# power.net
KiCad netlist of a schematic drawn in Altium Designer
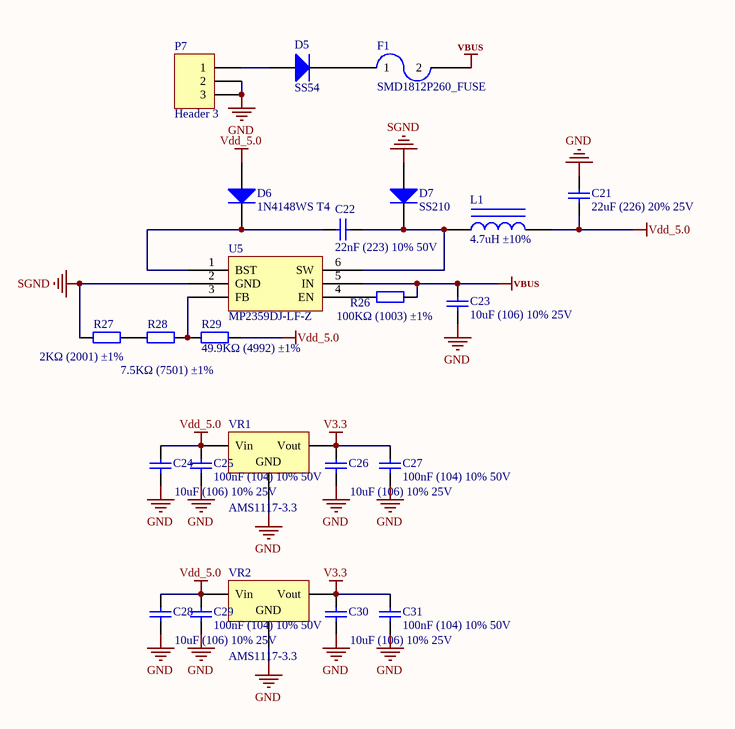
[diagram p0: power.SchDoc]

(export (version "E")
  (design (tool "Eeschema 10.0.6"))
  (components
    (comp (ref "C21")
      (value "22uF (226) 20% 25V")
      (footprint "0805_C")
      (description "贴片电容")
      (libsource (lib "Miscellaneous Devices LC") (part "0805 22uF (226) 20% 25V"))
    )
    (comp (ref "C22")
      (value "22nF (223) 10% 50V")
      (footprint "0603_C")
      (description "贴片电容")
      (libsource (lib "Miscellaneous Devices LC") (part "0603 22nF (223) 10% 50V"))
    )
    (comp (ref "C23")
      (value "10uF (106) 10% 25V")
      (footprint "0805_C")
      (description "贴片电容")
      (libsource (lib "Miscellaneous Devices LC") (part "0805 10uF (106) 10% 25V"))
    )
    (comp (ref "C24")
      (value "10uF (106) 10% 25V")
      (footprint "0805_C")
      (description "贴片电容")
      (libsource (lib "Miscellaneous Devices LC") (part "0805 10uF (106) 10% 25V"))
    )
    (comp (ref "C25")
      (value "100nF (104) 10% 50V")
      (footprint "0603_C")
      (description "贴片电容")
      (libsource (lib "Miscellaneous Devices LC") (part "0603 100nF (104) 10% 50V"))
    )
    (comp (ref "C26")
      (value "10uF (106) 10% 25V")
      (footprint "0805_C")
      (description "贴片电容")
      (libsource (lib "Miscellaneous Devices LC") (part "0805 10uF (106) 10% 25V"))
    )
    (comp (ref "C27")
      (value "100nF (104) 10% 50V")
      (footprint "0603_C")
      (description "贴片电容")
      (libsource (lib "Miscellaneous Devices LC") (part "0603 100nF (104) 10% 50V"))
    )
    (comp (ref "C28")
      (value "10uF (106) 10% 25V")
      (footprint "0805_C")
      (description "贴片电容")
      (libsource (lib "Miscellaneous Devices LC") (part "0805 10uF (106) 10% 25V"))
    )
    (comp (ref "C29")
      (value "100nF (104) 10% 50V")
      (footprint "0603_C")
      (description "贴片电容")
      (libsource (lib "Miscellaneous Devices LC") (part "0603 100nF (104) 10% 50V"))
    )
    (comp (ref "C30")
      (value "10uF (106) 10% 25V")
      (footprint "0805_C")
      (description "贴片电容")
      (libsource (lib "Miscellaneous Devices LC") (part "0805 10uF (106) 10% 25V"))
    )
    (comp (ref "C31")
      (value "100nF (104) 10% 50V")
      (footprint "0603_C")
      (description "贴片电容")
      (libsource (lib "Miscellaneous Devices LC") (part "0603 100nF (104) 10% 50V"))
    )
    (comp (ref "D5")
      (value "SS54")
      (footprint "SMA(DO-214AC)_S1")
      (description "二极管")
      (libsource (lib "Miscellaneous Devices LC") (part "SMA(DO-214AC) SS54"))
    )
    (comp (ref "D6")
      (value "1N4148WS T4")
      (footprint "SOD-323")
      (description "二极管")
      (libsource (lib "Miscellaneous Devices LC") (part "SOD-323 1N4148WS T4"))
    )
    (comp (ref "D7")
      (value "SS210")
      (footprint "SMA(DO-214AC)_S1")
      (description "二极管")
      (libsource (lib "Miscellaneous Devices LC") (part "SMA(DO-214AC) SS210"))
    )
    (comp (ref "F1")
      (value "SMD1812P260_FUSE")
      (footprint "SMD1812P260")
      (libsource (lib "mylib") (part "SMD1812P260_FUSE"))
    )
    (comp (ref "L1")
      (value "4.7uH ±10%")
      (footprint "L_4030")
      (description "贴片电感")
      (libsource (lib "Miscellaneous Devices LC") (part "0603 4.7uH 10%"))
    )
    (comp (ref "P7")
      (value "Header 3")
      (footprint "DC-005")
      (description "Header, 3-Pin")
      (fields (field (name "PUBLISHER") "Altium Limited"))
      (libsource (lib "Miscellaneous Connectors") (part "Header 3"))
    )
    (comp (ref "R26")
      (value "100KΩ (1003) ±1%")
      (footprint "0603_R")
      (description "贴片电阻")
      (libsource (lib "Miscellaneous Devices LC") (part "0603 100KΩ (1003) 1%"))
    )
    (comp (ref "R27")
      (value "2KΩ (2001) ±1%")
      (footprint "0603_R")
      (description "贴片电阻")
      (libsource (lib "Miscellaneous Devices LC") (part "0603 2KΩ (2001) 1%"))
    )
    (comp (ref "R28")
      (value "7.5KΩ (7501) ±1%")
      (footprint "0603_R")
      (description "贴片电阻")
      (libsource (lib "Miscellaneous Devices LC") (part "0603 7.5KΩ (7501) 1%"))
    )
    (comp (ref "R29")
      (value "49.9KΩ (4992) ±1%")
      (footprint "0603_R")
      (description "贴片电阻")
      (libsource (lib "Miscellaneous Devices LC") (part "0603 49.9KΩ (4992) 1%"))
    )
    (comp (ref "U5")
      (value "MP2359DJ-LF-Z")
      (footprint "SOT-23-6")
      (description "DC-DC芯片")
      (libsource (lib "Miscellaneous Devices LC") (part "MP2359DJ-LF-Z_[C14259]"))
    )
    (comp (ref "VR1")
      (value "AMS1117-3.3")
      (footprint "SOT-223")
      (description "低压差线性稳压(LDO)")
      (libsource (lib "Miscellaneous Devices LC") (part "SOT-223 AMS1117-3.3"))
    )
    (comp (ref "VR2")
      (value "AMS1117-3.3")
      (footprint "SOT-223")
      (description "低压差线性稳压(LDO)")
      (libsource (lib "Miscellaneous Devices LC") (part "SOT-223 AMS1117-3.3"))
    )
  )
  (nets
    (net (code "1") (name "GND") (class "Default")
      (node (ref "C21") (pin "2") (pinfunction "2_2") (pintype "passive"))
      (node (ref "C23") (pin "1") (pinfunction "1_1") (pintype "passive"))
      (node (ref "C24") (pin "1") (pinfunction "1_1") (pintype "passive"))
      (node (ref "C25") (pin "1") (pinfunction "1_1") (pintype "passive"))
      (node (ref "C26") (pin "1") (pinfunction "1_1") (pintype "passive"))
      (node (ref "C27") (pin "1") (pinfunction "1_1") (pintype "passive"))
      (node (ref "C28") (pin "1") (pinfunction "1_1") (pintype "passive"))
      (node (ref "C29") (pin "1") (pinfunction "1_1") (pintype "passive"))
      (node (ref "C30") (pin "1") (pinfunction "1_1") (pintype "passive"))
      (node (ref "C31") (pin "1") (pinfunction "1_1") (pintype "passive"))
      (node (ref "P7") (pin "2") (pinfunction "2_2") (pintype "passive"))
      (node (ref "P7") (pin "3") (pinfunction "3_3") (pintype "passive"))
      (node (ref "VR1") (pin "1") (pinfunction "GND_1") (pintype "passive"))
      (node (ref "VR2") (pin "1") (pinfunction "GND_1") (pintype "passive"))
    )
    (net (code "2") (name "Net-(D5-A)") (class "Default")
      (node (ref "D5") (pin "1") (pinfunction "A_1") (pintype "passive"))
      (node (ref "P7") (pin "1") (pinfunction "1_1") (pintype "passive"))
    )
    (net (code "3") (name "Net-(D5-K)") (class "Default")
      (node (ref "D5") (pin "2") (pinfunction "K_2") (pintype "passive"))
      (node (ref "F1") (pin "1") (pinfunction "1_1") (pintype "passive"))
    )
    (net (code "4") (name "Net-(D6-K)") (class "Default")
      (node (ref "C22") (pin "1") (pinfunction "1_1") (pintype "passive"))
      (node (ref "D6") (pin "2") (pinfunction "K_2") (pintype "passive"))
      (node (ref "U5") (pin "1") (pinfunction "BST_1") (pintype "passive"))
    )
    (net (code "5") (name "Net-(D7-K)") (class "Default")
      (node (ref "C22") (pin "2") (pinfunction "2_2") (pintype "passive"))
      (node (ref "D7") (pin "2") (pinfunction "K_2") (pintype "passive"))
      (node (ref "L1") (pin "1") (pinfunction "1_1") (pintype "passive"))
      (node (ref "U5") (pin "6") (pinfunction "SW_6") (pintype "passive"))
    )
    (net (code "6") (name "Net-(R27-Pad1)") (class "Default")
      (node (ref "R27") (pin "1") (pinfunction "1_1") (pintype "passive"))
      (node (ref "R28") (pin "2") (pinfunction "2_2") (pintype "passive"))
    )
    (net (code "7") (name "Net-(U5-EN)") (class "Default")
      (node (ref "R26") (pin "1") (pinfunction "1_1") (pintype "passive"))
      (node (ref "U5") (pin "4") (pinfunction "EN_4") (pintype "passive"))
    )
    (net (code "8") (name "Net-(U5-FB)") (class "Default")
      (node (ref "R28") (pin "1") (pinfunction "1_1") (pintype "passive"))
      (node (ref "R29") (pin "1") (pinfunction "1_1") (pintype "passive"))
      (node (ref "U5") (pin "3") (pinfunction "FB_3") (pintype "passive"))
    )
    (net (code "9") (name "SGND") (class "Default")
      (node (ref "D7") (pin "1") (pinfunction "A_1") (pintype "passive"))
      (node (ref "R27") (pin "2") (pinfunction "2_2") (pintype "passive"))
      (node (ref "U5") (pin "2") (pinfunction "GND_2") (pintype "passive"))
    )
    (net (code "10") (name "V3.3") (class "Default")
      (node (ref "C26") (pin "2") (pinfunction "2_2") (pintype "passive"))
      (node (ref "C27") (pin "2") (pinfunction "2_2") (pintype "passive"))
      (node (ref "C30") (pin "2") (pinfunction "2_2") (pintype "passive"))
      (node (ref "C31") (pin "2") (pinfunction "2_2") (pintype "passive"))
      (node (ref "VR1") (pin "2") (pinfunction "Vout_2") (pintype "passive"))
      (node (ref "VR2") (pin "2") (pinfunction "Vout_2") (pintype "passive"))
    )
    (net (code "11") (name "VBUS") (class "Default")
      (node (ref "C23") (pin "2") (pinfunction "2_2") (pintype "passive"))
      (node (ref "F1") (pin "2") (pinfunction "2_2") (pintype "passive"))
      (node (ref "R26") (pin "2") (pinfunction "2_2") (pintype "passive"))
      (node (ref "U5") (pin "5") (pinfunction "IN_5") (pintype "passive"))
    )
    (net (code "12") (name "Vdd_5.0") (class "Default")
      (node (ref "C21") (pin "1") (pinfunction "1_1") (pintype "passive"))
      (node (ref "C24") (pin "2") (pinfunction "2_2") (pintype "passive"))
      (node (ref "C25") (pin "2") (pinfunction "2_2") (pintype "passive"))
      (node (ref "C28") (pin "2") (pinfunction "2_2") (pintype "passive"))
      (node (ref "C29") (pin "2") (pinfunction "2_2") (pintype "passive"))
      (node (ref "D6") (pin "1") (pinfunction "A_1") (pintype "passive"))
      (node (ref "L1") (pin "2") (pinfunction "2_2") (pintype "passive"))
      (node (ref "R29") (pin "2") (pinfunction "2_2") (pintype "passive"))
      (node (ref "VR1") (pin "3") (pinfunction "Vin_3") (pintype "passive"))
      (node (ref "VR2") (pin "3") (pinfunction "Vin_3") (pintype "passive"))
    )
  )
)
